# valhalla-electrics.net
KiCad netlist of a schematic drawn in EAGLE
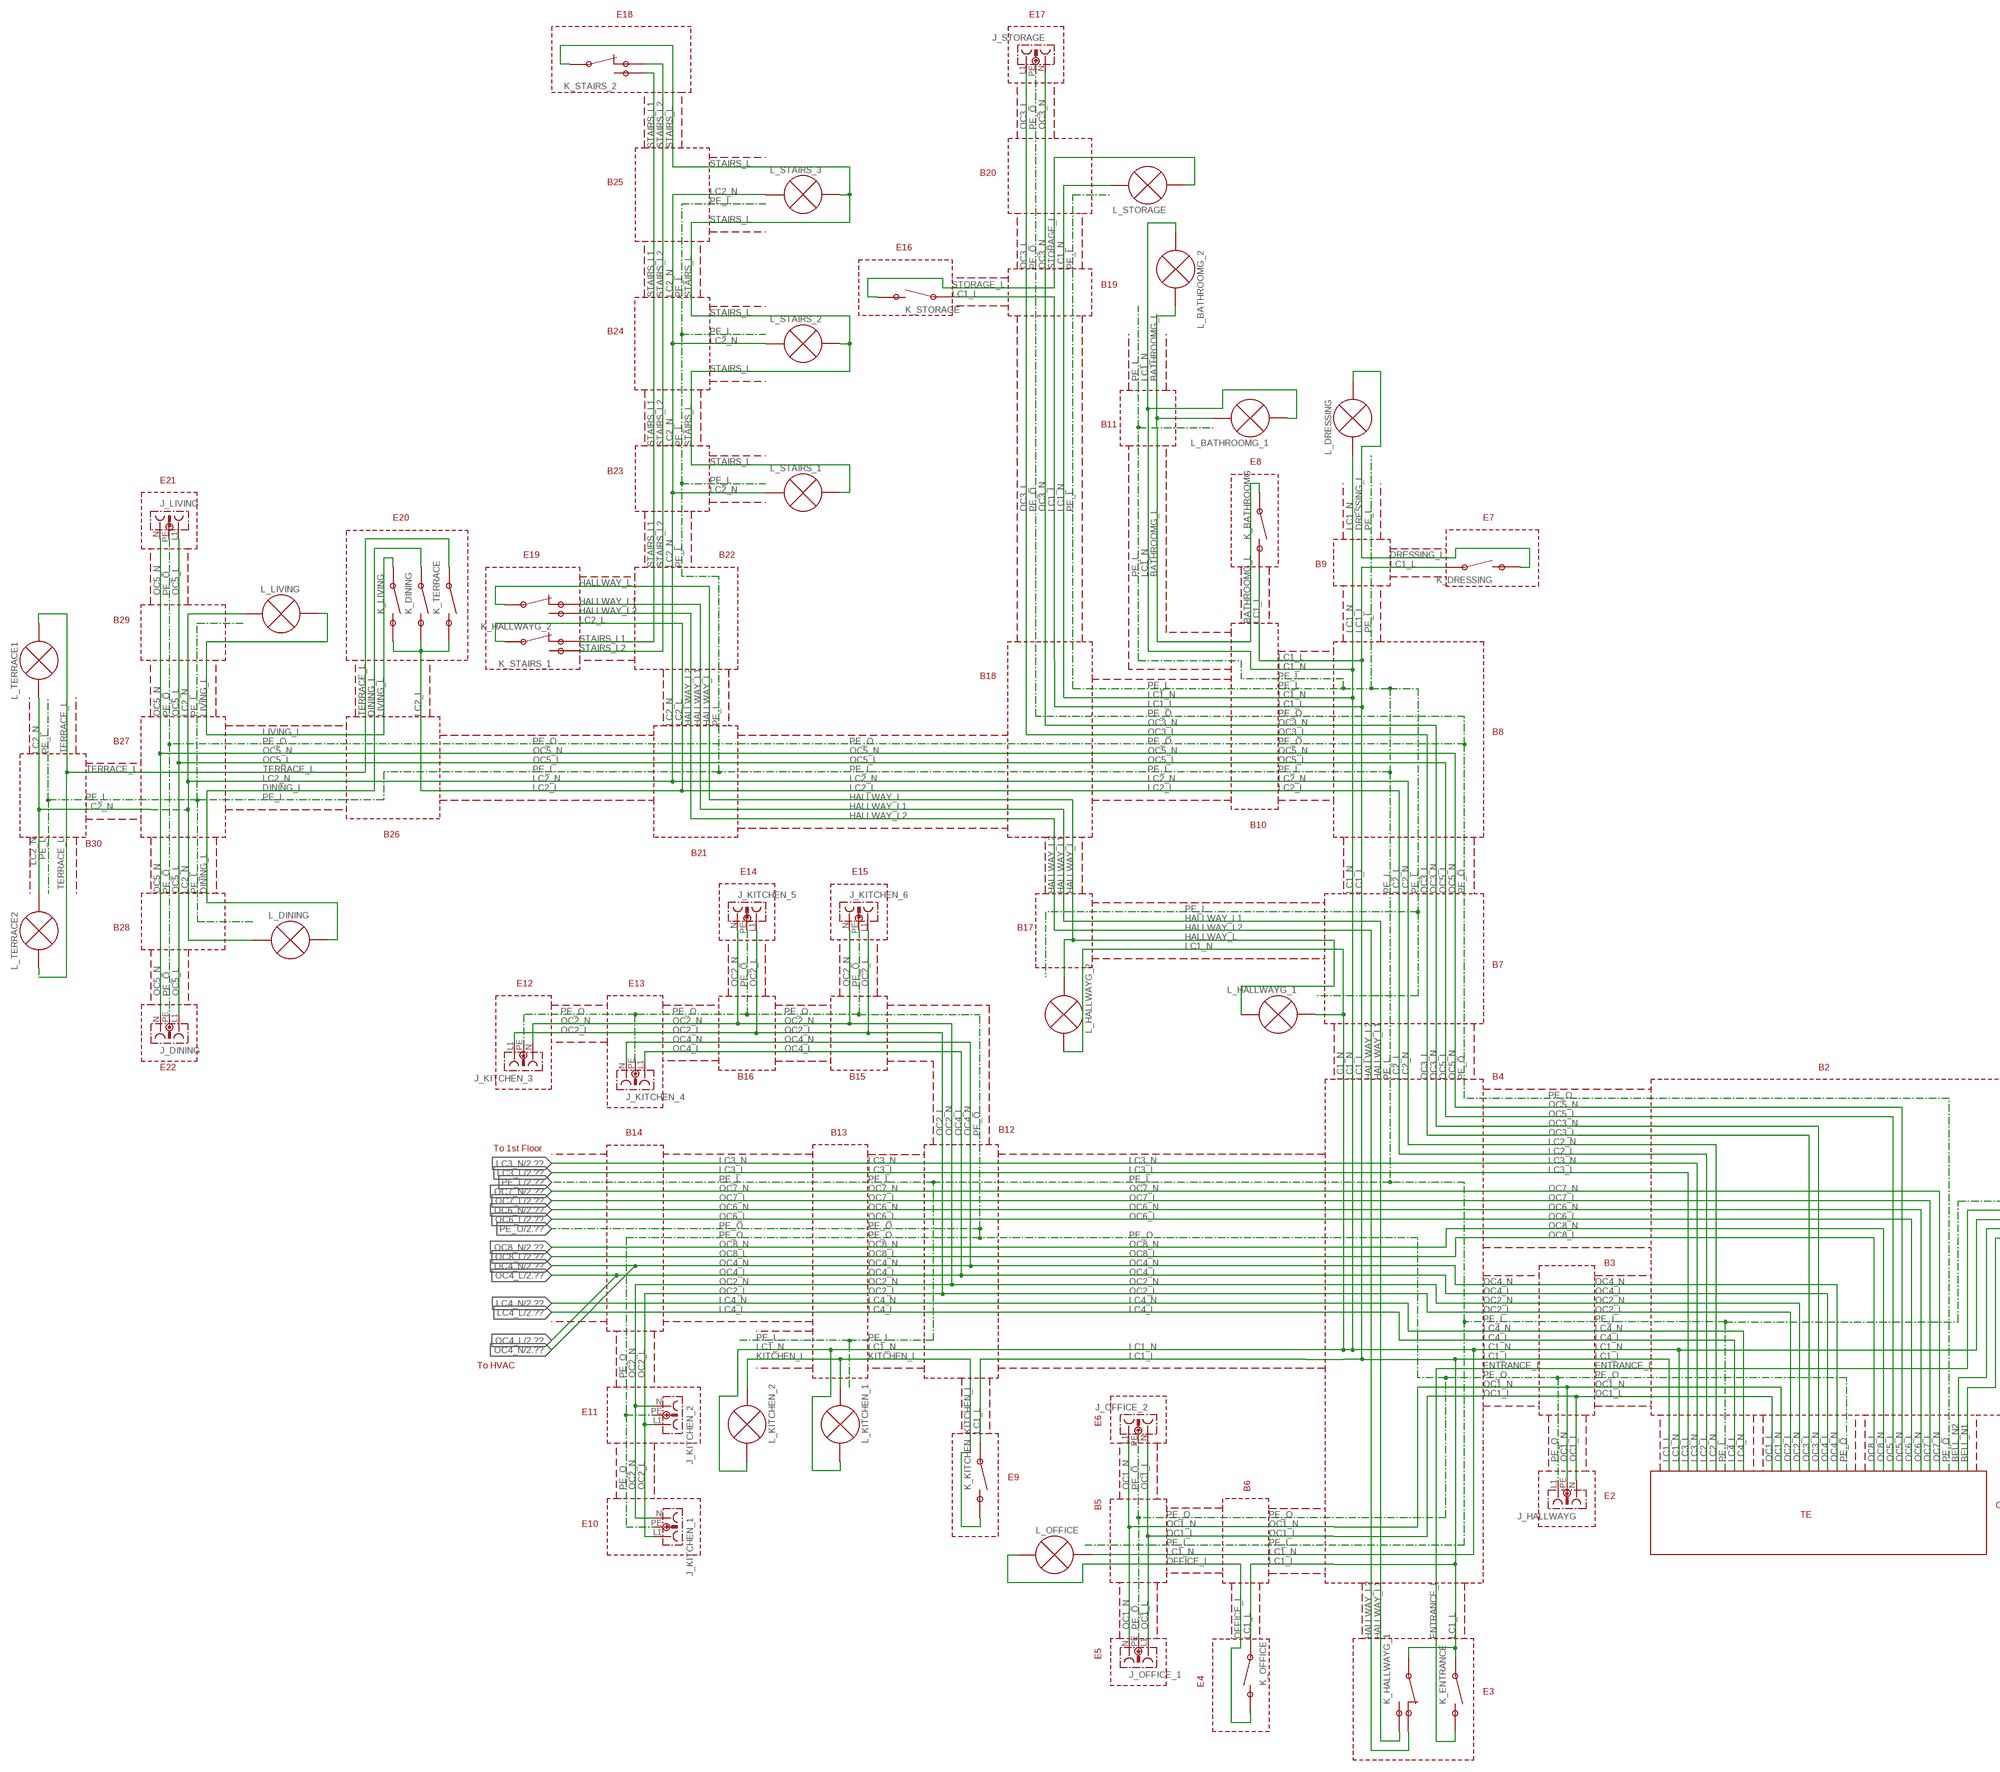
[diagram p0: schematic, sheet 1, part 1 of 2]
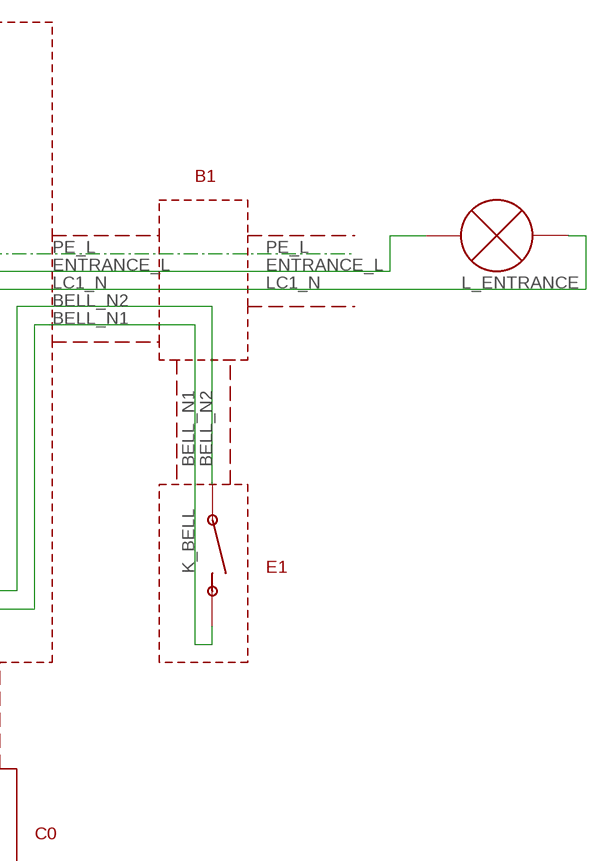
[diagram p1: schematic, sheet 1, part 2 of 2]
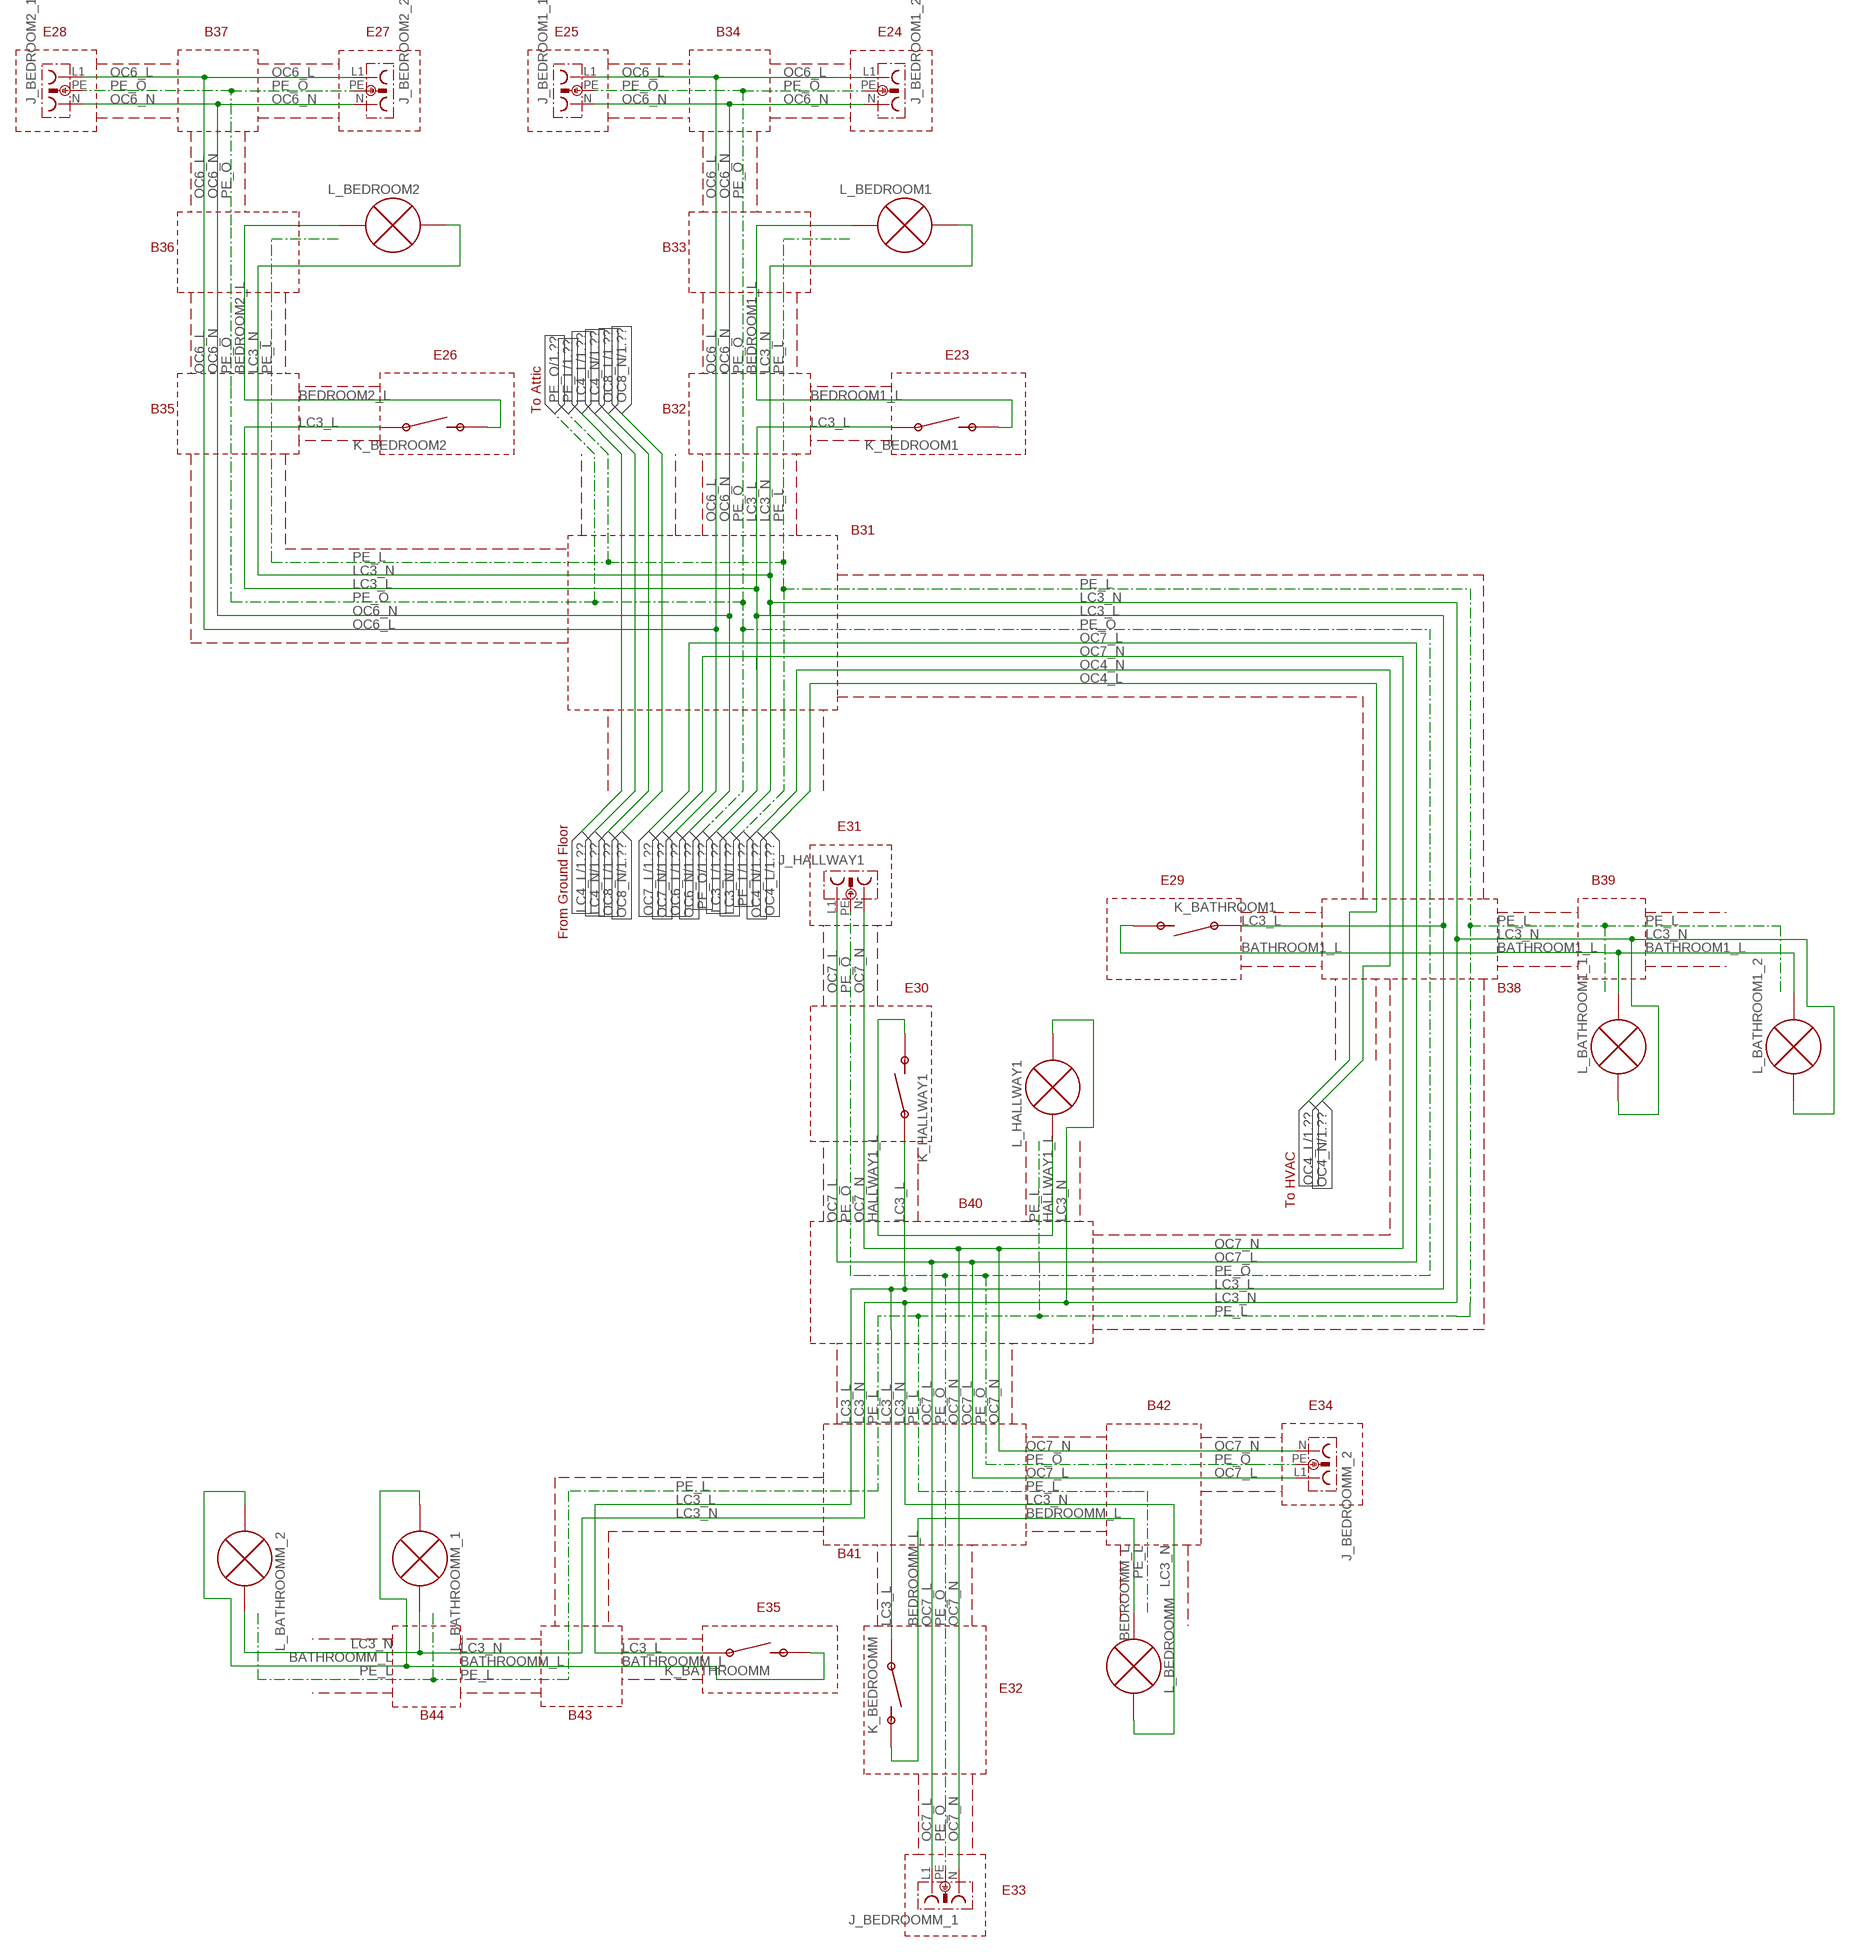
[diagram p2: schematic, sheet 2]

(export (version "E")
  (design (tool "Eeschema 10.0.6"))
  (components
    (comp (ref "J_DINING")
      (value "STECKDOSE")
      (footprint "eagle-import:STECKDOSE")
      (libsource (lib "eagle-import") (part "STECKDOSE"))
    )
    (comp (ref "J_HALLWAYG")
      (value "STECKDOSE")
      (footprint "eagle-import:STECKDOSE")
      (libsource (lib "eagle-import") (part "STECKDOSE"))
    )
    (comp (ref "J_KITCHEN_1")
      (value "STECKDOSE")
      (footprint "eagle-import:STECKDOSE")
      (libsource (lib "eagle-import") (part "STECKDOSE"))
    )
    (comp (ref "J_KITCHEN_2")
      (value "STECKDOSE")
      (footprint "eagle-import:STECKDOSE")
      (libsource (lib "eagle-import") (part "STECKDOSE"))
    )
    (comp (ref "J_KITCHEN_3")
      (value "STECKDOSE")
      (footprint "eagle-import:STECKDOSE")
      (libsource (lib "eagle-import") (part "STECKDOSE"))
    )
    (comp (ref "J_KITCHEN_4")
      (value "STECKDOSE")
      (footprint "eagle-import:STECKDOSE")
      (libsource (lib "eagle-import") (part "STECKDOSE"))
    )
    (comp (ref "J_KITCHEN_5")
      (value "STECKDOSE")
      (footprint "eagle-import:STECKDOSE")
      (libsource (lib "eagle-import") (part "STECKDOSE"))
    )
    (comp (ref "J_KITCHEN_6")
      (value "STECKDOSE")
      (footprint "eagle-import:STECKDOSE")
      (libsource (lib "eagle-import") (part "STECKDOSE"))
    )
    (comp (ref "J_LIVING")
      (value "STECKDOSE")
      (footprint "eagle-import:STECKDOSE")
      (libsource (lib "eagle-import") (part "STECKDOSE"))
    )
    (comp (ref "J_OFFICE_1")
      (value "STECKDOSE")
      (footprint "eagle-import:STECKDOSE")
      (libsource (lib "eagle-import") (part "STECKDOSE"))
    )
    (comp (ref "J_OFFICE_2")
      (value "STECKDOSE")
      (footprint "eagle-import:STECKDOSE")
      (libsource (lib "eagle-import") (part "STECKDOSE"))
    )
    (comp (ref "J_STORAGE")
      (value "STECKDOSE")
      (footprint "eagle-import:STECKDOSE")
      (libsource (lib "eagle-import") (part "STECKDOSE"))
    )
    (comp (ref "J_BEDROOM1_1")
      (value "STECKDOSE")
      (footprint "eagle-import:STECKDOSE")
      (libsource (lib "eagle-import") (part "STECKDOSE"))
    )
    (comp (ref "J_BEDROOM1_2")
      (value "STECKDOSE")
      (footprint "eagle-import:STECKDOSE")
      (libsource (lib "eagle-import") (part "STECKDOSE"))
    )
    (comp (ref "J_BEDROOM2_1")
      (value "STECKDOSE")
      (footprint "eagle-import:STECKDOSE")
      (libsource (lib "eagle-import") (part "STECKDOSE"))
    )
    (comp (ref "J_BEDROOM2_2")
      (value "STECKDOSE")
      (footprint "eagle-import:STECKDOSE")
      (libsource (lib "eagle-import") (part "STECKDOSE"))
    )
    (comp (ref "J_BEDROOMM_1")
      (value "STECKDOSE")
      (footprint "eagle-import:STECKDOSE")
      (libsource (lib "eagle-import") (part "STECKDOSE"))
    )
    (comp (ref "J_BEDROOMM_2")
      (value "STECKDOSE")
      (footprint "eagle-import:STECKDOSE")
      (libsource (lib "eagle-import") (part "STECKDOSE"))
    )
    (comp (ref "J_HALLWAY1")
      (value "STECKDOSE")
      (footprint "eagle-import:STECKDOSE")
      (libsource (lib "eagle-import") (part "STECKDOSE"))
    )
  )
  (nets
    (net (code "26") (name "OC1_L") (class "Default")
      (node (ref "J_HALLWAYG") (pin "N") (pinfunction "N_N") (pintype "passive"))
      (node (ref "J_OFFICE_1") (pin "L1") (pinfunction "L1_L1") (pintype "passive"))
      (node (ref "J_OFFICE_2") (pin "N") (pinfunction "N_N") (pintype "passive"))
    )
    (net (code "27") (name "OC1_N") (class "Default")
      (node (ref "J_HALLWAYG") (pin "PE") (pinfunction "PE_PE") (pintype "passive"))
      (node (ref "J_OFFICE_1") (pin "N") (pinfunction "N_N") (pintype "passive"))
      (node (ref "J_OFFICE_2") (pin "L1") (pinfunction "L1_L1") (pintype "passive"))
    )
    (net (code "28") (name "OC2_L") (class "Default")
      (node (ref "J_KITCHEN_1") (pin "L1") (pinfunction "L1_L1") (pintype "passive"))
      (node (ref "J_KITCHEN_2") (pin "L1") (pinfunction "L1_L1") (pintype "passive"))
      (node (ref "J_KITCHEN_3") (pin "L1") (pinfunction "L1_L1") (pintype "passive"))
      (node (ref "J_KITCHEN_5") (pin "L1") (pinfunction "L1_L1") (pintype "passive"))
      (node (ref "J_KITCHEN_6") (pin "L1") (pinfunction "L1_L1") (pintype "passive"))
    )
    (net (code "29") (name "OC2_N") (class "Default")
      (node (ref "J_KITCHEN_1") (pin "N") (pinfunction "N_N") (pintype "passive"))
      (node (ref "J_KITCHEN_2") (pin "N") (pinfunction "N_N") (pintype "passive"))
      (node (ref "J_KITCHEN_3") (pin "N") (pinfunction "N_N") (pintype "passive"))
      (node (ref "J_KITCHEN_5") (pin "N") (pinfunction "N_N") (pintype "passive"))
      (node (ref "J_KITCHEN_6") (pin "N") (pinfunction "N_N") (pintype "passive"))
    )
    (net (code "30") (name "OC3_L") (class "Default")
      (node (ref "J_STORAGE") (pin "L1") (pinfunction "L1_L1") (pintype "passive"))
    )
    (net (code "31") (name "OC3_N") (class "Default")
      (node (ref "J_STORAGE") (pin "N") (pinfunction "N_N") (pintype "passive"))
    )
    (net (code "32") (name "OC4_L") (class "Default")
      (node (ref "J_KITCHEN_4") (pin "L1") (pinfunction "L1_L1") (pintype "passive"))
    )
    (net (code "33") (name "OC4_N") (class "Default")
      (node (ref "J_KITCHEN_4") (pin "N") (pinfunction "N_N") (pintype "passive"))
    )
    (net (code "34") (name "OC5_L") (class "Default")
      (node (ref "J_DINING") (pin "L1") (pinfunction "L1_L1") (pintype "passive"))
      (node (ref "J_LIVING") (pin "L1") (pinfunction "L1_L1") (pintype "passive"))
    )
    (net (code "35") (name "OC5_N") (class "Default")
      (node (ref "J_DINING") (pin "N") (pinfunction "N_N") (pintype "passive"))
      (node (ref "J_LIVING") (pin "N") (pinfunction "N_N") (pintype "passive"))
    )
    (net (code "36") (name "OC6_L") (class "Default")
      (node (ref "J_BEDROOM1_1") (pin "L1") (pinfunction "L1_L1") (pintype "passive"))
      (node (ref "J_BEDROOM1_2") (pin "L1") (pinfunction "L1_L1") (pintype "passive"))
      (node (ref "J_BEDROOM2_1") (pin "L1") (pinfunction "L1_L1") (pintype "passive"))
      (node (ref "J_BEDROOM2_2") (pin "L1") (pinfunction "L1_L1") (pintype "passive"))
    )
    (net (code "37") (name "OC6_N") (class "Default")
      (node (ref "J_BEDROOM1_1") (pin "N") (pinfunction "N_N") (pintype "passive"))
      (node (ref "J_BEDROOM1_2") (pin "N") (pinfunction "N_N") (pintype "passive"))
      (node (ref "J_BEDROOM2_1") (pin "N") (pinfunction "N_N") (pintype "passive"))
      (node (ref "J_BEDROOM2_2") (pin "N") (pinfunction "N_N") (pintype "passive"))
    )
    (net (code "38") (name "OC7_L") (class "Default")
      (node (ref "J_BEDROOMM_1") (pin "L1") (pinfunction "L1_L1") (pintype "passive"))
      (node (ref "J_BEDROOMM_2") (pin "L1") (pinfunction "L1_L1") (pintype "passive"))
      (node (ref "J_HALLWAY1") (pin "L1") (pinfunction "L1_L1") (pintype "passive"))
    )
    (net (code "39") (name "OC7_N") (class "Default")
      (node (ref "J_BEDROOMM_1") (pin "N") (pinfunction "N_N") (pintype "passive"))
      (node (ref "J_BEDROOMM_2") (pin "N") (pinfunction "N_N") (pintype "passive"))
      (node (ref "J_HALLWAY1") (pin "N") (pinfunction "N_N") (pintype "passive"))
    )
    (net (code "44") (name "PE_O") (class "Default")
      (node (ref "J_BEDROOM1_1") (pin "PE") (pinfunction "PE_PE") (pintype "passive"))
      (node (ref "J_BEDROOM1_2") (pin "PE") (pinfunction "PE_PE") (pintype "passive"))
      (node (ref "J_BEDROOM2_1") (pin "PE") (pinfunction "PE_PE") (pintype "passive"))
      (node (ref "J_BEDROOM2_2") (pin "PE") (pinfunction "PE_PE") (pintype "passive"))
      (node (ref "J_BEDROOMM_1") (pin "PE") (pinfunction "PE_PE") (pintype "passive"))
      (node (ref "J_BEDROOMM_2") (pin "PE") (pinfunction "PE_PE") (pintype "passive"))
      (node (ref "J_DINING") (pin "PE") (pinfunction "PE_PE") (pintype "passive"))
      (node (ref "J_HALLWAY1") (pin "PE") (pinfunction "PE_PE") (pintype "passive"))
      (node (ref "J_HALLWAYG") (pin "L1") (pinfunction "L1_L1") (pintype "passive"))
      (node (ref "J_KITCHEN_1") (pin "PE") (pinfunction "PE_PE") (pintype "passive"))
      (node (ref "J_KITCHEN_2") (pin "PE") (pinfunction "PE_PE") (pintype "passive"))
      (node (ref "J_KITCHEN_3") (pin "PE") (pinfunction "PE_PE") (pintype "passive"))
      (node (ref "J_KITCHEN_4") (pin "PE") (pinfunction "PE_PE") (pintype "passive"))
      (node (ref "J_KITCHEN_5") (pin "PE") (pinfunction "PE_PE") (pintype "passive"))
      (node (ref "J_KITCHEN_6") (pin "PE") (pinfunction "PE_PE") (pintype "passive"))
      (node (ref "J_LIVING") (pin "PE") (pinfunction "PE_PE") (pintype "passive"))
      (node (ref "J_OFFICE_1") (pin "PE") (pinfunction "PE_PE") (pintype "passive"))
      (node (ref "J_OFFICE_2") (pin "PE") (pinfunction "PE_PE") (pintype "passive"))
      (node (ref "J_STORAGE") (pin "PE") (pinfunction "PE_PE") (pintype "passive"))
    )
  )
)
